# connectivity.net
KiCad netlist of a schematic drawn in Altium Designer
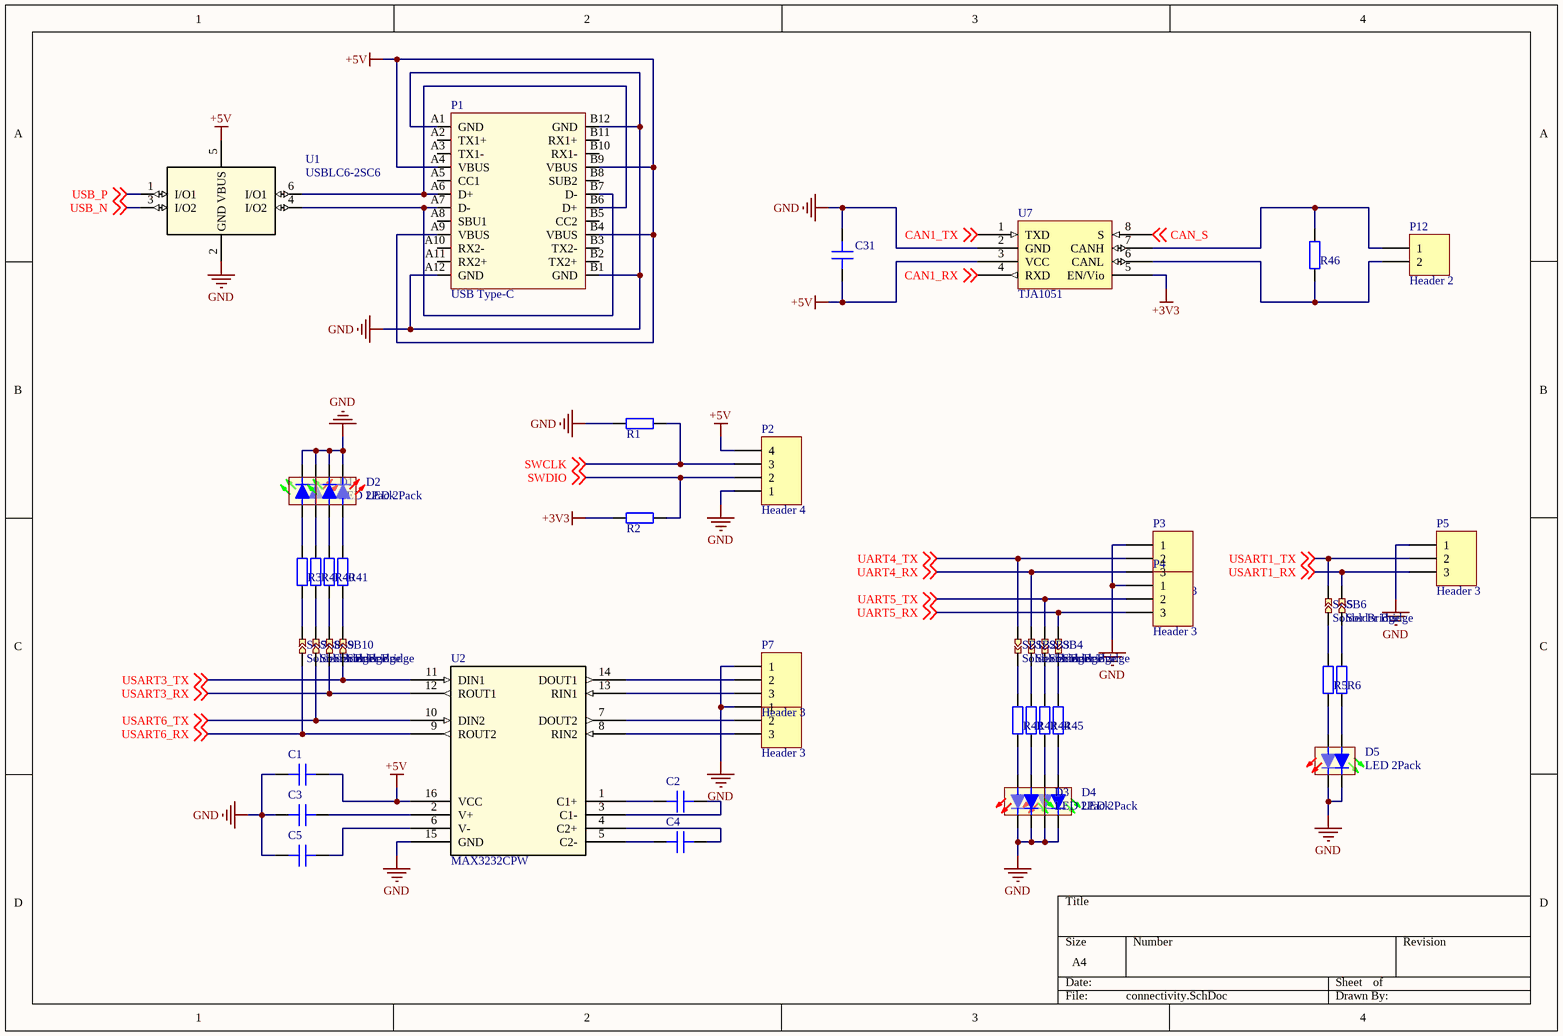
[diagram p0: connectivity.SchDoc]

(export (version "E")
  (design (tool "Eeschema 10.0.6"))
  (components
    (comp (ref "C1")
      (value "100nF")
      (footprint "CAP 0805")
      (description "Non-polar capacitor")
      (fields (field (name "PUBLISHER") "Altium Limited"))
      (libsource (lib "MiLib") (part "Cap"))
    )
    (comp (ref "C2")
      (value "100nF")
      (footprint "CAP 0805")
      (description "Non-polar capacitor")
      (fields (field (name "PUBLISHER") "Altium Limited"))
      (libsource (lib "MiLib") (part "Cap"))
    )
    (comp (ref "C3")
      (value "100nF")
      (footprint "CAP 0805")
      (description "Non-polar capacitor")
      (fields (field (name "PUBLISHER") "Altium Limited"))
      (libsource (lib "MiLib") (part "Cap"))
    )
    (comp (ref "C4")
      (value "100nF")
      (footprint "CAP 0805")
      (description "Non-polar capacitor")
      (fields (field (name "PUBLISHER") "Altium Limited"))
      (libsource (lib "MiLib") (part "Cap"))
    )
    (comp (ref "C5")
      (value "100nF")
      (footprint "CAP 0805")
      (description "Non-polar capacitor")
      (fields (field (name "PUBLISHER") "Altium Limited"))
      (libsource (lib "MiLib") (part "Cap"))
    )
    (comp (ref "C31")
      (value "100nF")
      (footprint "CAP 0805")
      (description "Non-polar capacitor")
      (fields (field (name "PUBLISHER") "Altium Limited"))
      (libsource (lib "MiLib") (part "Cap"))
    )
    (comp (ref "D1")
      (value "LED 2Pack")
      (footprint "LED-1615")
      (description "Two seperate LEDs packed together.")
      (libsource (lib "") (part "LED 2Pack_1"))
    )
    (comp (ref "D2")
      (value "LED 2Pack")
      (footprint "LED-1615")
      (description "Two seperate LEDs packed together.")
      (libsource (lib "") (part "LED 2Pack_1"))
    )
    (comp (ref "D3")
      (value "LED 2Pack")
      (footprint "LED-1615")
      (description "Two seperate LEDs packed together.")
      (libsource (lib "MiLib") (part "LED 2Pack"))
    )
    (comp (ref "D4")
      (value "LED 2Pack")
      (footprint "LED-1615")
      (description "Two seperate LEDs packed together.")
      (libsource (lib "MiLib") (part "LED 2Pack"))
    )
    (comp (ref "D5")
      (value "LED 2Pack")
      (footprint "LED-1615")
      (description "Two seperate LEDs packed together.")
      (libsource (lib "MiLib") (part "LED 2Pack"))
    )
    (comp (ref "P1")
      (value "USB Type-C")
      (footprint "USB Type-C 24P")
      (libsource (lib "MiLib") (part "USB Type-C"))
    )
    (comp (ref "P2")
      (value "Header 4")
      (footprint "HDR1X4")
      (description "Header, 4-Pin")
      (fields (field (name "PUBLISHER") "Altium Limited"))
      (libsource (lib "MiLib") (part "Header 4"))
    )
    (comp (ref "P3")
      (value "Header 3")
      (footprint "MOLEX 53426-0310")
      (description "Header, 3-Pin")
      (fields (field (name "PUBLISHER") "Altium Limited"))
      (libsource (lib "MiLib") (part "Header 3"))
    )
    (comp (ref "P4")
      (value "Header 3")
      (footprint "MOLEX 53426-0310")
      (description "Header, 3-Pin")
      (fields (field (name "PUBLISHER") "Altium Limited"))
      (libsource (lib "MiLib") (part "Header 3"))
    )
    (comp (ref "P5")
      (value "Header 3")
      (footprint "MOLEX 53426-0310")
      (description "Header, 3-Pin")
      (fields (field (name "PUBLISHER") "Altium Limited"))
      (libsource (lib "MiLib") (part "Header 3"))
    )
    (comp (ref "P6")
      (value "Header 3")
      (footprint "MOLEX 53426-0310")
      (description "Header, 3-Pin")
      (fields (field (name "PUBLISHER") "Altium Limited"))
      (libsource (lib "MiLib") (part "Header 3"))
    )
    (comp (ref "P7")
      (value "Header 3")
      (footprint "MOLEX 53426-0310")
      (description "Header, 3-Pin")
      (fields (field (name "PUBLISHER") "Altium Limited"))
      (libsource (lib "MiLib") (part "Header 3"))
    )
    (comp (ref "P12")
      (value "Header 2")
      (footprint "MOLEX 53426-0210")
      (description "Header, 2-Pin")
      (fields (field (name "PUBLISHER") "Altium Limited"))
      (libsource (lib "MiLib") (part "Header 2"))
    )
    (comp (ref "R1")
      (value "10kOhm")
      (footprint "RES 0805")
      (description "Resistor")
      (fields (field (name "PUBLISHER") "Altium Limited"))
      (libsource (lib "") (part "Res_1"))
    )
    (comp (ref "R2")
      (value "10kOhm")
      (footprint "RES 0805")
      (description "Resistor")
      (fields (field (name "PUBLISHER") "Altium Limited"))
      (libsource (lib "") (part "Res_1"))
    )
    (comp (ref "R3")
      (value "10kOhm")
      (footprint "RES 0805")
      (description "Resistor")
      (fields (field (name "PUBLISHER") "Altium Limited"))
      (libsource (lib "MiLib") (part "Res"))
    )
    (comp (ref "R4")
      (value "10kOhm")
      (footprint "RES 0805")
      (description "Resistor")
      (fields (field (name "PUBLISHER") "Altium Limited"))
      (libsource (lib "MiLib") (part "Res"))
    )
    (comp (ref "R5")
      (value "10kOhm")
      (footprint "RES 0805")
      (description "Resistor")
      (fields (field (name "PUBLISHER") "Altium Limited"))
      (libsource (lib "MiLib") (part "Res"))
    )
    (comp (ref "R6")
      (value "10kOhm")
      (footprint "RES 0805")
      (description "Resistor")
      (fields (field (name "PUBLISHER") "Altium Limited"))
      (libsource (lib "MiLib") (part "Res"))
    )
    (comp (ref "R40")
      (value "10kOhm")
      (footprint "RES 0805")
      (description "Resistor")
      (fields (field (name "PUBLISHER") "Altium Limited"))
      (libsource (lib "MiLib") (part "Res"))
    )
    (comp (ref "R41")
      (value "10kOhm")
      (footprint "RES 0805")
      (description "Resistor")
      (fields (field (name "PUBLISHER") "Altium Limited"))
      (libsource (lib "MiLib") (part "Res"))
    )
    (comp (ref "R42")
      (value "10kOhm")
      (footprint "RES 0805")
      (description "Resistor")
      (fields (field (name "PUBLISHER") "Altium Limited"))
      (libsource (lib "MiLib") (part "Res"))
    )
    (comp (ref "R43")
      (value "10kOhm")
      (footprint "RES 0805")
      (description "Resistor")
      (fields (field (name "PUBLISHER") "Altium Limited"))
      (libsource (lib "MiLib") (part "Res"))
    )
    (comp (ref "R44")
      (value "10kOhm")
      (footprint "RES 0805")
      (description "Resistor")
      (fields (field (name "PUBLISHER") "Altium Limited"))
      (libsource (lib "MiLib") (part "Res"))
    )
    (comp (ref "R45")
      (value "10kOhm")
      (footprint "RES 0805")
      (description "Resistor")
      (fields (field (name "PUBLISHER") "Altium Limited"))
      (libsource (lib "MiLib") (part "Res"))
    )
    (comp (ref "R46")
      (value "10kOhm")
      (footprint "RES 0805")
      (description "Resistor")
      (fields (field (name "PUBLISHER") "Altium Limited"))
      (libsource (lib "") (part "Res_2"))
    )
    (comp (ref "SB1")
      (value "Solder Bridge")
      (footprint "Solder Bridge")
      (libsource (lib "MiLib") (part "Solder Bridge"))
    )
    (comp (ref "SB2")
      (value "Solder Bridge")
      (footprint "Solder Bridge")
      (libsource (lib "MiLib") (part "Solder Bridge"))
    )
    (comp (ref "SB3")
      (value "Solder Bridge")
      (footprint "Solder Bridge")
      (libsource (lib "MiLib") (part "Solder Bridge"))
    )
    (comp (ref "SB4")
      (value "Solder Bridge")
      (footprint "Solder Bridge")
      (libsource (lib "MiLib") (part "Solder Bridge"))
    )
    (comp (ref "SB5")
      (value "Solder Bridge")
      (footprint "Solder Bridge")
      (libsource (lib "MiLib") (part "Solder Bridge"))
    )
    (comp (ref "SB6")
      (value "Solder Bridge")
      (footprint "Solder Bridge")
      (libsource (lib "MiLib") (part "Solder Bridge"))
    )
    (comp (ref "SB7")
      (value "Solder Bridge")
      (footprint "Solder Bridge")
      (libsource (lib "MiLib") (part "Solder Bridge"))
    )
    (comp (ref "SB8")
      (value "Solder Bridge")
      (footprint "Solder Bridge")
      (libsource (lib "MiLib") (part "Solder Bridge"))
    )
    (comp (ref "SB9")
      (value "Solder Bridge")
      (footprint "Solder Bridge")
      (libsource (lib "MiLib") (part "Solder Bridge"))
    )
    (comp (ref "SB10")
      (value "Solder Bridge")
      (footprint "Solder Bridge")
      (libsource (lib "MiLib") (part "Solder Bridge"))
    )
    (comp (ref "U1")
      (value "USBLC6-2SC6")
      (footprint "SOT23-6L_STM")
      (libsource (lib "misc") (part "USBLC6-2SC6"))
    )
    (comp (ref "U2")
      (value "MAX3232CPW")
      (footprint "TSSOP-16")
      (description "3-V to 5.5-V Multichannel RS-232 Line Driver/Receiver")
      (fields
        (field (name "MANUFACTURER") "Texas Instruments")
        (field (name "GENERIC_PART_NUMBER") "MAX3232")
        (field (name "COPYRIGHT") "Copyright (C) 2021 Accelerated Designs. All rights reserved")
      )
      (libsource (lib "misc") (part "MAX3232CPW"))
    )
    (comp (ref "U7")
      (value "TJA1051")
      (footprint "SO-8")
      (description "High-speed CAN transceiver")
      (libsource (lib "misc") (part "TJA1051"))
    )
  )
  (nets
    (net (code "1") (name "+3V3") (class "Default")
      (node (ref "R2") (pin "2") (pinfunction "2_2") (pintype "passive"))
      (node (ref "U7") (pin "5") (pinfunction "EN/Vio_5") (pintype "passive"))
    )
    (net (code "2") (name "+5V") (class "Default")
      (node (ref "C1") (pin "2") (pinfunction "2_2") (pintype "passive"))
      (node (ref "C31") (pin "1") (pinfunction "1_1") (pintype "passive"))
      (node (ref "P1") (pin "A4") (pinfunction "VBUS_A4") (pintype "passive"))
      (node (ref "P1") (pin "A9") (pinfunction "VBUS_A9") (pintype "passive"))
      (node (ref "P1") (pin "B4") (pinfunction "VBUS_B4") (pintype "passive"))
      (node (ref "P1") (pin "B9") (pinfunction "VBUS_B9") (pintype "passive"))
      (node (ref "P2") (pin "4") (pinfunction "4_4") (pintype "passive"))
      (node (ref "U1") (pin "5") (pinfunction "VBUS_5") (pintype "power_in"))
      (node (ref "U2") (pin "16") (pinfunction "VCC_16") (pintype "power_in"))
      (node (ref "U7") (pin "3") (pinfunction "VCC_3") (pintype "power_in"))
    )
    (net (code "3") (name "CAN1_RX") (class "Default")
      (node (ref "U7") (pin "4") (pinfunction "RXD_4") (pintype "output"))
    )
    (net (code "4") (name "CAN1_TX") (class "Default")
      (node (ref "U7") (pin "1") (pinfunction "TXD_1") (pintype "input"))
    )
    (net (code "5") (name "CAN_S") (class "Default")
      (node (ref "U7") (pin "8") (pinfunction "S_8") (pintype "input"))
    )
    (net (code "6") (name "GND") (class "Default")
      (node (ref "C1") (pin "1") (pinfunction "1_1") (pintype "passive"))
      (node (ref "C3") (pin "1") (pinfunction "1_1") (pintype "passive"))
      (node (ref "C31") (pin "2") (pinfunction "2_2") (pintype "passive"))
      (node (ref "C5") (pin "1") (pinfunction "1_1") (pintype "passive"))
      (node (ref "D1") (pin "1") (pinfunction "RK_1") (pintype "passive"))
      (node (ref "D1") (pin "2") (pinfunction "GK_2") (pintype "passive"))
      (node (ref "D2") (pin "1") (pinfunction "RK_1") (pintype "passive"))
      (node (ref "D2") (pin "2") (pinfunction "GK_2") (pintype "passive"))
      (node (ref "D3") (pin "1") (pinfunction "RK_1") (pintype "passive"))
      (node (ref "D3") (pin "2") (pinfunction "GK_2") (pintype "passive"))
      (node (ref "D4") (pin "1") (pinfunction "RK_1") (pintype "passive"))
      (node (ref "D4") (pin "2") (pinfunction "GK_2") (pintype "passive"))
      (node (ref "D5") (pin "1") (pinfunction "RK_1") (pintype "passive"))
      (node (ref "D5") (pin "2") (pinfunction "GK_2") (pintype "passive"))
      (node (ref "P1") (pin "A1") (pinfunction "GND_A1") (pintype "passive"))
      (node (ref "P1") (pin "A12") (pinfunction "GND_A12") (pintype "passive"))
      (node (ref "P1") (pin "B1") (pinfunction "GND_B1") (pintype "passive"))
      (node (ref "P1") (pin "B12") (pinfunction "GND_B12") (pintype "passive"))
      (node (ref "P2") (pin "1") (pinfunction "1_1") (pintype "passive"))
      (node (ref "P3") (pin "1") (pinfunction "1_1") (pintype "passive"))
      (node (ref "P4") (pin "1") (pinfunction "1_1") (pintype "passive"))
      (node (ref "P5") (pin "1") (pinfunction "1_1") (pintype "passive"))
      (node (ref "P6") (pin "1") (pinfunction "1_1") (pintype "passive"))
      (node (ref "P7") (pin "1") (pinfunction "1_1") (pintype "passive"))
      (node (ref "R1") (pin "2") (pinfunction "2_2") (pintype "passive"))
      (node (ref "U1") (pin "2") (pinfunction "GND_2") (pintype "power_in"))
      (node (ref "U2") (pin "15") (pinfunction "GND_15") (pintype "power_in"))
      (node (ref "U7") (pin "2") (pinfunction "GND_2") (pintype "power_in"))
    )
    (net (code "7") (name "Net-(D1-GA)") (class "Default")
      (node (ref "D1") (pin "3") (pinfunction "GA_3") (pintype "passive"))
      (node (ref "R3") (pin "2") (pinfunction "2_2") (pintype "passive"))
    )
    (net (code "8") (name "Net-(D1-RA)") (class "Default")
      (node (ref "D1") (pin "4") (pinfunction "RA_4") (pintype "passive"))
      (node (ref "R4") (pin "2") (pinfunction "2_2") (pintype "passive"))
    )
    (net (code "9") (name "Net-(D2-GA)") (class "Default")
      (node (ref "D2") (pin "3") (pinfunction "GA_3") (pintype "passive"))
      (node (ref "R40") (pin "2") (pinfunction "2_2") (pintype "passive"))
    )
    (net (code "10") (name "Net-(D2-RA)") (class "Default")
      (node (ref "D2") (pin "4") (pinfunction "RA_4") (pintype "passive"))
      (node (ref "R41") (pin "2") (pinfunction "2_2") (pintype "passive"))
    )
    (net (code "11") (name "Net-(D3-GA)") (class "Default")
      (node (ref "D3") (pin "3") (pinfunction "GA_3") (pintype "passive"))
      (node (ref "R43") (pin "1") (pinfunction "1_1") (pintype "passive"))
    )
    (net (code "12") (name "Net-(D3-RA)") (class "Default")
      (node (ref "D3") (pin "4") (pinfunction "RA_4") (pintype "passive"))
      (node (ref "R42") (pin "1") (pinfunction "1_1") (pintype "passive"))
    )
    (net (code "13") (name "Net-(D4-GA)") (class "Default")
      (node (ref "D4") (pin "3") (pinfunction "GA_3") (pintype "passive"))
      (node (ref "R45") (pin "1") (pinfunction "1_1") (pintype "passive"))
    )
    (net (code "14") (name "Net-(D4-RA)") (class "Default")
      (node (ref "D4") (pin "4") (pinfunction "RA_4") (pintype "passive"))
      (node (ref "R44") (pin "1") (pinfunction "1_1") (pintype "passive"))
    )
    (net (code "15") (name "Net-(D5-GA)") (class "Default")
      (node (ref "D5") (pin "3") (pinfunction "GA_3") (pintype "passive"))
      (node (ref "R6") (pin "1") (pinfunction "1_1") (pintype "passive"))
    )
    (net (code "16") (name "Net-(D5-RA)") (class "Default")
      (node (ref "D5") (pin "4") (pinfunction "RA_4") (pintype "passive"))
      (node (ref "R5") (pin "1") (pinfunction "1_1") (pintype "passive"))
    )
    (net (code "17") (name "Net-(P1-D+-PadA6)") (class "Default")
      (node (ref "P1") (pin "A6") (pinfunction "D+_A6") (pintype "passive"))
      (node (ref "P1") (pin "B6") (pinfunction "D+_B6") (pintype "passive"))
      (node (ref "U1") (pin "6") (pinfunction "I/O1_6") (pintype "bidirectional"))
    )
    (net (code "18") (name "Net-(P1-D--PadA7)") (class "Default")
      (node (ref "P1") (pin "A7") (pinfunction "D-_A7") (pintype "passive"))
      (node (ref "P1") (pin "B7") (pinfunction "D-_B7") (pintype "passive"))
      (node (ref "U1") (pin "4") (pinfunction "I/O2_4") (pintype "bidirectional"))
    )
    (net (code "19") (name "Net-(R3-Pad1)") (class "Default")
      (node (ref "R3") (pin "1") (pinfunction "1_1") (pintype "passive"))
      (node (ref "SB7") (pin "1") (pinfunction "1_1") (pintype "passive"))
    )
    (net (code "20") (name "Net-(R4-Pad1)") (class "Default")
      (node (ref "R4") (pin "1") (pinfunction "1_1") (pintype "passive"))
      (node (ref "SB8") (pin "1") (pinfunction "1_1") (pintype "passive"))
    )
    (net (code "21") (name "Net-(R5-Pad2)") (class "Default")
      (node (ref "R5") (pin "2") (pinfunction "2_2") (pintype "passive"))
      (node (ref "SB5") (pin "2") (pinfunction "2_2") (pintype "passive"))
    )
    (net (code "22") (name "Net-(R6-Pad2)") (class "Default")
      (node (ref "R6") (pin "2") (pinfunction "2_2") (pintype "passive"))
      (node (ref "SB6") (pin "2") (pinfunction "2_2") (pintype "passive"))
    )
    (net (code "23") (name "Net-(R40-Pad1)") (class "Default")
      (node (ref "R40") (pin "1") (pinfunction "1_1") (pintype "passive"))
      (node (ref "SB9") (pin "1") (pinfunction "1_1") (pintype "passive"))
    )
    (net (code "24") (name "Net-(R41-Pad1)") (class "Default")
      (node (ref "R41") (pin "1") (pinfunction "1_1") (pintype "passive"))
      (node (ref "SB10") (pin "1") (pinfunction "1_1") (pintype "passive"))
    )
    (net (code "25") (name "Net-(R42-Pad2)") (class "Default")
      (node (ref "R42") (pin "2") (pinfunction "2_2") (pintype "passive"))
      (node (ref "SB1") (pin "1") (pinfunction "1_1") (pintype "passive"))
    )
    (net (code "26") (name "Net-(R43-Pad2)") (class "Default")
      (node (ref "R43") (pin "2") (pinfunction "2_2") (pintype "passive"))
      (node (ref "SB2") (pin "1") (pinfunction "1_1") (pintype "passive"))
    )
    (net (code "27") (name "Net-(R44-Pad2)") (class "Default")
      (node (ref "R44") (pin "2") (pinfunction "2_2") (pintype "passive"))
      (node (ref "SB3") (pin "1") (pinfunction "1_1") (pintype "passive"))
    )
    (net (code "28") (name "Net-(R45-Pad2)") (class "Default")
      (node (ref "R45") (pin "2") (pinfunction "2_2") (pintype "passive"))
      (node (ref "SB4") (pin "1") (pinfunction "1_1") (pintype "passive"))
    )
    (net (code "29") (name "Net-(U2-C1+)") (class "Default")
      (node (ref "C2") (pin "1") (pinfunction "1_1") (pintype "passive"))
      (node (ref "U2") (pin "1") (pinfunction "C1+_1") (pintype "passive"))
    )
    (net (code "30") (name "Net-(U2-C1-)") (class "Default")
      (node (ref "C2") (pin "2") (pinfunction "2_2") (pintype "passive"))
      (node (ref "U2") (pin "3") (pinfunction "C1-_3") (pintype "passive"))
    )
    (net (code "31") (name "Net-(U2-C2+)") (class "Default")
      (node (ref "C4") (pin "2") (pinfunction "2_2") (pintype "passive"))
      (node (ref "U2") (pin "4") (pinfunction "C2+_4") (pintype "passive"))
    )
    (net (code "32") (name "Net-(U2-C2-)") (class "Default")
      (node (ref "C4") (pin "1") (pinfunction "1_1") (pintype "passive"))
      (node (ref "U2") (pin "5") (pinfunction "C2-_5") (pintype "passive"))
    )
    (net (code "33") (name "Net-(U2-DOUT1)") (class "Default")
      (node (ref "P7") (pin "2") (pinfunction "2_2") (pintype "passive"))
      (node (ref "U2") (pin "14") (pinfunction "DOUT1_14") (pintype "output"))
    )
    (net (code "34") (name "Net-(U2-DOUT2)") (class "Default")
      (node (ref "P6") (pin "2") (pinfunction "2_2") (pintype "passive"))
      (node (ref "U2") (pin "7") (pinfunction "DOUT2_7") (pintype "output"))
    )
    (net (code "35") (name "Net-(U2-RIN1)") (class "Default")
      (node (ref "P7") (pin "3") (pinfunction "3_3") (pintype "passive"))
      (node (ref "U2") (pin "13") (pinfunction "RIN1_13") (pintype "input"))
    )
    (net (code "36") (name "Net-(U2-RIN2)") (class "Default")
      (node (ref "P6") (pin "3") (pinfunction "3_3") (pintype "passive"))
      (node (ref "U2") (pin "8") (pinfunction "RIN2_8") (pintype "input"))
    )
    (net (code "37") (name "Net-(U2-V+)") (class "Default")
      (node (ref "C3") (pin "2") (pinfunction "2_2") (pintype "passive"))
      (node (ref "U2") (pin "2") (pinfunction "V+_2") (pintype "power_in"))
    )
    (net (code "38") (name "Net-(U2-V-)") (class "Default")
      (node (ref "C5") (pin "2") (pinfunction "2_2") (pintype "passive"))
      (node (ref "U2") (pin "6") (pinfunction "V-_6") (pintype "power_in"))
    )
    (net (code "39") (name "Net-(U7-CANH)") (class "Default")
      (node (ref "P12") (pin "1") (pinfunction "1_1") (pintype "passive"))
      (node (ref "R46") (pin "1") (pinfunction "1_1") (pintype "passive"))
      (node (ref "U7") (pin "7") (pinfunction "CANH_7") (pintype "bidirectional"))
    )
    (net (code "40") (name "Net-(U7-CANL)") (class "Default")
      (node (ref "P12") (pin "2") (pinfunction "2_2") (pintype "passive"))
      (node (ref "R46") (pin "2") (pinfunction "2_2") (pintype "passive"))
      (node (ref "U7") (pin "6") (pinfunction "CANL_6") (pintype "bidirectional"))
    )
    (net (code "41") (name "SWCLK") (class "Default")
      (node (ref "P2") (pin "3") (pinfunction "3_3") (pintype "passive"))
      (node (ref "R1") (pin "1") (pinfunction "1_1") (pintype "passive"))
    )
    (net (code "42") (name "SWDIO") (class "Default")
      (node (ref "P2") (pin "2") (pinfunction "2_2") (pintype "passive"))
      (node (ref "R2") (pin "1") (pinfunction "1_1") (pintype "passive"))
    )
    (net (code "43") (name "UART4_RX") (class "Default")
      (node (ref "P3") (pin "3") (pinfunction "3_3") (pintype "passive"))
      (node (ref "SB2") (pin "2") (pinfunction "2_2") (pintype "passive"))
    )
    (net (code "44") (name "UART4_TX") (class "Default")
      (node (ref "P3") (pin "2") (pinfunction "2_2") (pintype "passive"))
      (node (ref "SB1") (pin "2") (pinfunction "2_2") (pintype "passive"))
    )
    (net (code "45") (name "UART5_RX") (class "Default")
      (node (ref "P4") (pin "3") (pinfunction "3_3") (pintype "passive"))
      (node (ref "SB4") (pin "2") (pinfunction "2_2") (pintype "passive"))
    )
    (net (code "46") (name "UART5_TX") (class "Default")
      (node (ref "P4") (pin "2") (pinfunction "2_2") (pintype "passive"))
      (node (ref "SB3") (pin "2") (pinfunction "2_2") (pintype "passive"))
    )
    (net (code "47") (name "USART1_RX") (class "Default")
      (node (ref "P5") (pin "3") (pinfunction "3_3") (pintype "passive"))
      (node (ref "SB6") (pin "1") (pinfunction "1_1") (pintype "passive"))
    )
    (net (code "48") (name "USART1_TX") (class "Default")
      (node (ref "P5") (pin "2") (pinfunction "2_2") (pintype "passive"))
      (node (ref "SB5") (pin "1") (pinfunction "1_1") (pintype "passive"))
    )
    (net (code "49") (name "USART3_RX") (class "Default")
      (node (ref "SB9") (pin "2") (pinfunction "2_2") (pintype "passive"))
      (node (ref "U2") (pin "12") (pinfunction "ROUT1_12") (pintype "output"))
    )
    (net (code "50") (name "USART3_TX") (class "Default")
      (node (ref "SB10") (pin "2") (pinfunction "2_2") (pintype "passive"))
      (node (ref "U2") (pin "11") (pinfunction "DIN1_11") (pintype "input"))
    )
    (net (code "51") (name "USART6_RX") (class "Default")
      (node (ref "SB7") (pin "2") (pinfunction "2_2") (pintype "passive"))
      (node (ref "U2") (pin "9") (pinfunction "ROUT2_9") (pintype "output"))
    )
    (net (code "52") (name "USART6_TX") (class "Default")
      (node (ref "SB8") (pin "2") (pinfunction "2_2") (pintype "passive"))
      (node (ref "U2") (pin "10") (pinfunction "DIN2_10") (pintype "input"))
    )
    (net (code "53") (name "USB_N") (class "Default")
      (node (ref "U1") (pin "3") (pinfunction "I/O2_3") (pintype "bidirectional"))
    )
    (net (code "54") (name "USB_P") (class "Default")
      (node (ref "U1") (pin "1") (pinfunction "I/O1_1") (pintype "bidirectional"))
    )
    (net (code "55") (name "unconnected-(P1-CC1-PadA5)") (class "Default")
      (node (ref "P1") (pin "A5") (pinfunction "CC1_A5") (pintype "passive"))
    )
    (net (code "56") (name "unconnected-(P1-CC2-PadB5)") (class "Default")
      (node (ref "P1") (pin "B5") (pinfunction "CC2_B5") (pintype "passive"))
    )
    (net (code "57") (name "unconnected-(P1-RX1+-PadB11)") (class "Default")
      (node (ref "P1") (pin "B11") (pinfunction "RX1+_B11") (pintype "passive"))
    )
    (net (code "58") (name "unconnected-(P1-RX1--PadB10)") (class "Default")
      (node (ref "P1") (pin "B10") (pinfunction "RX1-_B10") (pintype "passive"))
    )
    (net (code "59") (name "unconnected-(P1-RX2+-PadA11)") (class "Default")
      (node (ref "P1") (pin "A11") (pinfunction "RX2+_A11") (pintype "passive"))
    )
    (net (code "60") (name "unconnected-(P1-RX2--PadA10)") (class "Default")
      (node (ref "P1") (pin "A10") (pinfunction "RX2-_A10") (pintype "passive"))
    )
    (net (code "61") (name "unconnected-(P1-SBU1-PadA8)") (class "Default")
      (node (ref "P1") (pin "A8") (pinfunction "SBU1_A8") (pintype "passive"))
    )
    (net (code "62") (name "unconnected-(P1-SUB2-PadB8)") (class "Default")
      (node (ref "P1") (pin "B8") (pinfunction "SUB2_B8") (pintype "passive"))
    )
    (net (code "63") (name "unconnected-(P1-TX1+-PadA2)") (class "Default")
      (node (ref "P1") (pin "A2") (pinfunction "TX1+_A2") (pintype "passive"))
    )
    (net (code "64") (name "unconnected-(P1-TX1--PadA3)") (class "Default")
      (node (ref "P1") (pin "A3") (pinfunction "TX1-_A3") (pintype "passive"))
    )
    (net (code "65") (name "unconnected-(P1-TX2+-PadB2)") (class "Default")
      (node (ref "P1") (pin "B2") (pinfunction "TX2+_B2") (pintype "passive"))
    )
    (net (code "66") (name "unconnected-(P1-TX2--PadB3)") (class "Default")
      (node (ref "P1") (pin "B3") (pinfunction "TX2-_B3") (pintype "passive"))
    )
  )
)
